# driver_motor.net
KiCad netlist of a schematic drawn in EAGLE
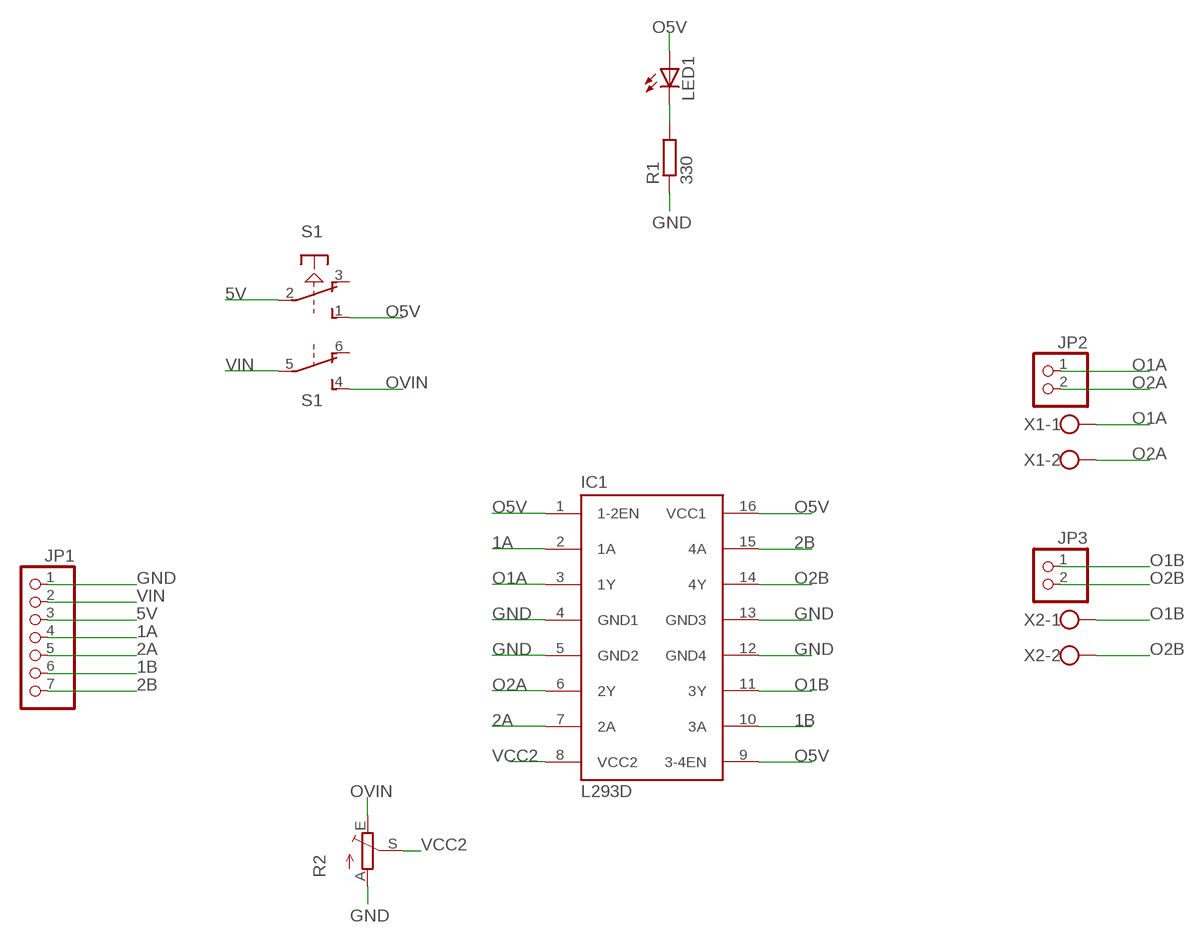
[diagram p0: schematic, sheet 1]

(export (version "E")
  (design (tool "Eeschema 10.0.6"))
  (components
    (comp (ref "IC1")
      (value "L293D")
      (footprint "eagle-import:DIL16")
      (libsource (lib "eagle-import") (part "L293D"))
    )
    (comp (ref "JP1")
      (value "PINHD-1X7")
      (footprint "eagle-import:1X07")
      (libsource (lib "eagle-import") (part "PINHD-1X7"))
    )
    (comp (ref "JP2")
      (value "PINHD-1X2")
      (footprint "eagle-import:1X02")
      (libsource (lib "eagle-import") (part "PINHD-1X2"))
    )
    (comp (ref "JP3")
      (value "PINHD-1X2")
      (footprint "eagle-import:1X02")
      (libsource (lib "eagle-import") (part "PINHD-1X2"))
    )
    (comp (ref "LED1")
      (value "LED3MM")
      (footprint "eagle-import:LED3MM")
      (libsource (lib "eagle-import") (part "LED3MM"))
    )
    (comp (ref "R1")
      (value "330")
      (footprint "eagle-import:0207_7")
      (libsource (lib "eagle-import") (part "R-EU_0207/7"))
    )
    (comp (ref "R2")
      (value "TRIM_EU-CA6V")
      (footprint "eagle-import:CA6V")
      (libsource (lib "eagle-import") (part "TRIM_EU-CA6V"))
    )
    (comp (ref "S1")
      (value "PVA2R")
      (footprint "eagle-import:PVA2R")
      (libsource (lib "eagle-import") (part "PVA2R"))
    )
    (comp (ref "X1")
      (value "W237-102")
      (footprint "eagle-import:W237-102")
      (fields (field (name "MPN") "237-102"))
      (libsource (lib "eagle-import") (part "W237-102"))
    )
    (comp (ref "X2")
      (value "W237-102")
      (footprint "eagle-import:W237-102")
      (fields (field (name "MPN") "237-102"))
      (libsource (lib "eagle-import") (part "W237-102"))
    )
  )
  (nets
    (net (code "1") (name "/1A") (class "Default")
      (node (ref "IC1") (pin "2") (pinfunction "1A_2") (pintype "input"))
      (node (ref "JP1") (pin "4") (pinfunction "4_4") (pintype "passive"))
    )
    (net (code "2") (name "/1B") (class "Default")
      (node (ref "IC1") (pin "10") (pinfunction "3A_10") (pintype "input"))
      (node (ref "JP1") (pin "6") (pinfunction "6_6") (pintype "passive"))
    )
    (net (code "3") (name "/2A") (class "Default")
      (node (ref "IC1") (pin "7") (pinfunction "2A_7") (pintype "input"))
      (node (ref "JP1") (pin "5") (pinfunction "5_5") (pintype "passive"))
    )
    (net (code "4") (name "/2B") (class "Default")
      (node (ref "IC1") (pin "15") (pinfunction "4A_15") (pintype "input"))
      (node (ref "JP1") (pin "7") (pinfunction "7_7") (pintype "passive"))
    )
    (net (code "5") (name "/5V") (class "Default")
      (node (ref "JP1") (pin "3") (pinfunction "3_3") (pintype "passive"))
      (node (ref "S1") (pin "2") (pinfunction "P_2") (pintype "passive"))
    )
    (net (code "6") (name "/GND") (class "Default")
      (node (ref "IC1") (pin "12") (pinfunction "GND4_12") (pintype "power_in"))
      (node (ref "IC1") (pin "13") (pinfunction "GND3_13") (pintype "power_in"))
      (node (ref "IC1") (pin "4") (pinfunction "GND1_4") (pintype "power_in"))
      (node (ref "IC1") (pin "5") (pinfunction "GND2_5") (pintype "power_in"))
      (node (ref "JP1") (pin "1") (pinfunction "1_1") (pintype "passive"))
      (node (ref "R1") (pin "1") (pinfunction "1_1") (pintype "passive"))
      (node (ref "R2") (pin "A") (pinfunction "A_A") (pintype "passive"))
    )
    (net (code "7") (name "/O1A") (class "Default")
      (node (ref "IC1") (pin "3") (pinfunction "1Y_3") (pintype "output"))
      (node (ref "JP2") (pin "1") (pinfunction "1_1") (pintype "passive"))
      (node (ref "X1") (pin "1") (pinfunction "KL_1") (pintype "passive"))
    )
    (net (code "8") (name "/O1B") (class "Default")
      (node (ref "IC1") (pin "11") (pinfunction "3Y_11") (pintype "output"))
      (node (ref "JP3") (pin "1") (pinfunction "1_1") (pintype "passive"))
      (node (ref "X2") (pin "1") (pinfunction "KL_1") (pintype "passive"))
    )
    (net (code "9") (name "/O2A") (class "Default")
      (node (ref "IC1") (pin "6") (pinfunction "2Y_6") (pintype "output"))
      (node (ref "JP2") (pin "2") (pinfunction "2_2") (pintype "passive"))
      (node (ref "X1") (pin "2") (pinfunction "KL_2") (pintype "passive"))
    )
    (net (code "10") (name "/O2B") (class "Default")
      (node (ref "IC1") (pin "14") (pinfunction "4Y_14") (pintype "output"))
      (node (ref "JP3") (pin "2") (pinfunction "2_2") (pintype "passive"))
      (node (ref "X2") (pin "2") (pinfunction "KL_2") (pintype "passive"))
    )
    (net (code "11") (name "/O5V") (class "Default")
      (node (ref "IC1") (pin "1") (pinfunction "1-2EN_1") (pintype "input"))
      (node (ref "IC1") (pin "16") (pinfunction "VCC1_16") (pintype "power_in"))
      (node (ref "IC1") (pin "9") (pinfunction "3-4EN_9") (pintype "input"))
      (node (ref "LED1") (pin "A") (pinfunction "A_A") (pintype "passive"))
      (node (ref "S1") (pin "1") (pinfunction "S_1") (pintype "passive"))
    )
    (net (code "12") (name "/OVIN") (class "Default")
      (node (ref "R2") (pin "E") (pinfunction "E_E") (pintype "passive"))
      (node (ref "S1") (pin "4") (pinfunction "S_4") (pintype "passive"))
    )
    (net (code "13") (name "/VCC2") (class "Default")
      (node (ref "IC1") (pin "8") (pinfunction "VCC2_8") (pintype "power_in"))
      (node (ref "R2") (pin "S") (pinfunction "S_S") (pintype "passive"))
    )
    (net (code "14") (name "/VIN") (class "Default")
      (node (ref "JP1") (pin "2") (pinfunction "2_2") (pintype "passive"))
      (node (ref "S1") (pin "5") (pinfunction "P_5") (pintype "passive"))
    )
    (net (code "15") (name "Net-(LED1-C)") (class "Default")
      (node (ref "LED1") (pin "K") (pinfunction "C_K") (pintype "passive"))
      (node (ref "R1") (pin "2") (pinfunction "2_2") (pintype "passive"))
    )
    (net (code "16") (name "unconnected-(S1A-O-Pad3)") (class "Default")
      (node (ref "S1") (pin "3") (pinfunction "O_3") (pintype "passive"))
    )
    (net (code "17") (name "unconnected-(S1B-O-Pad6)") (class "Default")
      (node (ref "S1") (pin "6") (pinfunction "O_6") (pintype "passive"))
    )
  )
)
